# PRE_amp_16_5.net
KiCad netlist of a schematic drawn in EAGLE
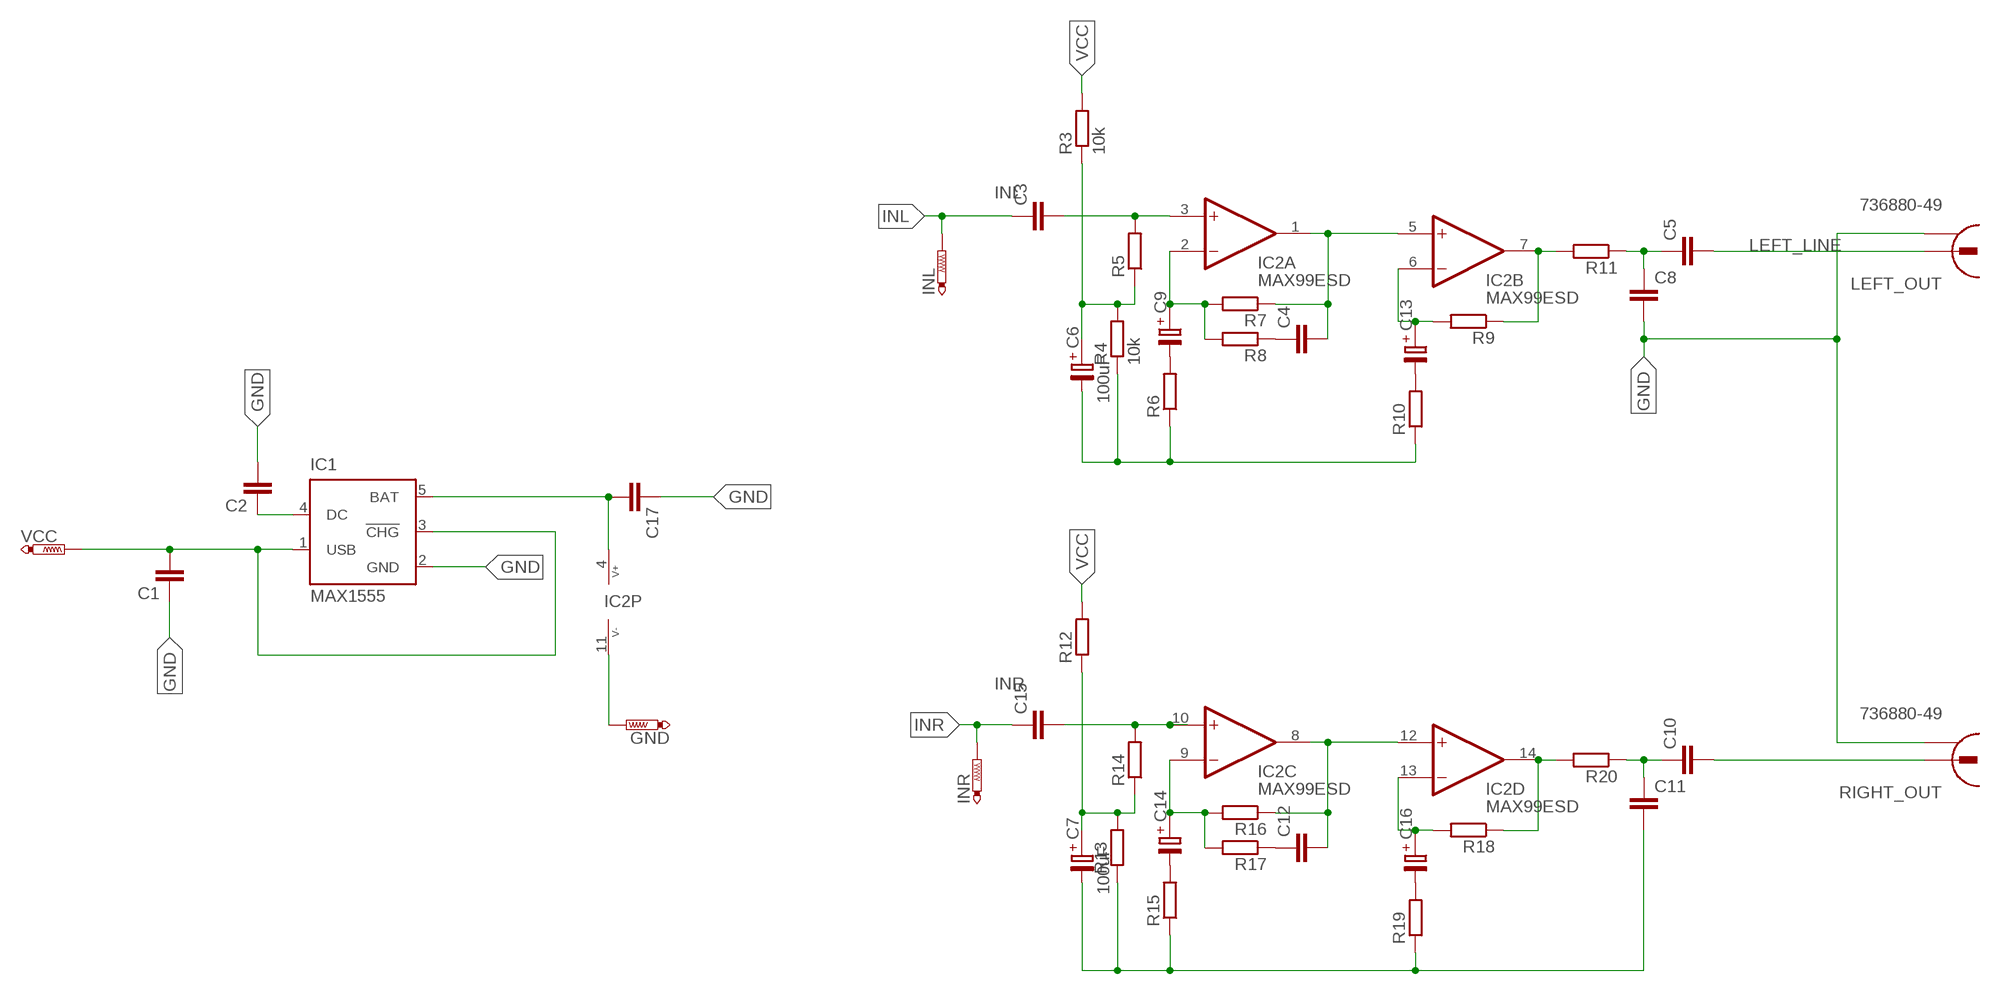
[diagram p0: schematic, sheet 1]

(export (version "E")
  (design (tool "Eeschema 10.0.6"))
  (components
    (comp (ref "C1")
      (value "C-EUC0805")
      (footprint "eagle-import:C0805")
      (libsource (lib "eagle-import") (part "C-EUC0805"))
    )
    (comp (ref "C2")
      (value "C-EUC0805")
      (footprint "eagle-import:C0805")
      (libsource (lib "eagle-import") (part "C-EUC0805"))
    )
    (comp (ref "C3")
      (value "C-EUC0805")
      (footprint "eagle-import:C0805")
      (libsource (lib "eagle-import") (part "C-EUC0805"))
    )
    (comp (ref "C4")
      (value "C-EUC0805")
      (footprint "eagle-import:C0805")
      (libsource (lib "eagle-import") (part "C-EUC0805"))
    )
    (comp (ref "C5")
      (value "C-EUC0805")
      (footprint "eagle-import:C0805")
      (libsource (lib "eagle-import") (part "C-EUC0805"))
    )
    (comp (ref "C6")
      (value "100uF")
      (footprint "eagle-import:SV-D")
      (libsource (lib "eagle-import") (part "C-PR-SMD-SV-D"))
    )
    (comp (ref "C7")
      (value "100uF")
      (footprint "eagle-import:SV-D")
      (libsource (lib "eagle-import") (part "C-PR-SMD-SV-D"))
    )
    (comp (ref "C8")
      (value "C-EUC0805")
      (footprint "eagle-import:C0805")
      (libsource (lib "eagle-import") (part "C-EUC0805"))
    )
    (comp (ref "C9")
      (value "C-PR-SMD-SV-B")
      (footprint "eagle-import:SV-B")
      (libsource (lib "eagle-import") (part "C-PR-SMD-SV-B"))
    )
    (comp (ref "C10")
      (value "C-EUC0805")
      (footprint "eagle-import:C0805")
      (libsource (lib "eagle-import") (part "C-EUC0805"))
    )
    (comp (ref "C11")
      (value "C-EUC0805")
      (footprint "eagle-import:C0805")
      (libsource (lib "eagle-import") (part "C-EUC0805"))
    )
    (comp (ref "C12")
      (value "C-EUC0805")
      (footprint "eagle-import:C0805")
      (libsource (lib "eagle-import") (part "C-EUC0805"))
    )
    (comp (ref "C13")
      (value "C-PR-SMD-SV-B")
      (footprint "eagle-import:SV-B")
      (libsource (lib "eagle-import") (part "C-PR-SMD-SV-B"))
    )
    (comp (ref "C14")
      (value "C-PR-SMD-SV-B")
      (footprint "eagle-import:SV-B")
      (libsource (lib "eagle-import") (part "C-PR-SMD-SV-B"))
    )
    (comp (ref "C15")
      (value "C-EUC0805")
      (footprint "eagle-import:C0805")
      (libsource (lib "eagle-import") (part "C-EUC0805"))
    )
    (comp (ref "C16")
      (value "C-PR-SMD-SV-B")
      (footprint "eagle-import:SV-B")
      (libsource (lib "eagle-import") (part "C-PR-SMD-SV-B"))
    )
    (comp (ref "C17")
      (value "C-EUC0805")
      (footprint "eagle-import:C0805")
      (libsource (lib "eagle-import") (part "C-EUC0805"))
    )
    (comp (ref "GND")
      (value "PTR1PAD1-13Y")
      (footprint "eagle-import:P1-13Y")
      (libsource (lib "eagle-import") (part "PTR1PAD1-13Y"))
    )
    (comp (ref "IC1")
      (value "MAX1555")
      (footprint "eagle-import:SOT23-5L")
      (libsource (lib "eagle-import") (part "MAX1555"))
    )
    (comp (ref "IC2")
      (value "MAX99ESD")
      (footprint "eagle-import:SO14")
      (libsource (lib "eagle-import") (part "MAX99ESD"))
    )
    (comp (ref "INL")
      (value "PTR1PAD1-13Y")
      (footprint "eagle-import:P1-13Y")
      (libsource (lib "eagle-import") (part "PTR1PAD1-13Y"))
    )
    (comp (ref "INR")
      (value "PTR1PAD1-13Y")
      (footprint "eagle-import:P1-13Y")
      (libsource (lib "eagle-import") (part "PTR1PAD1-13Y"))
    )
    (comp (ref "LEFT_OUT")
      (value "736880-49")
      (footprint "eagle-import:736880-49")
      (libsource (lib "eagle-import") (part "736880-49"))
    )
    (comp (ref "R3")
      (value "10k")
      (footprint "eagle-import:R1206")
      (libsource (lib "eagle-import") (part "R-EU_R1206"))
    )
    (comp (ref "R4")
      (value "10k")
      (footprint "eagle-import:R1206")
      (libsource (lib "eagle-import") (part "R-EU_R1206"))
    )
    (comp (ref "R5")
      (value "R-EU_R1206")
      (footprint "eagle-import:R1206")
      (libsource (lib "eagle-import") (part "R-EU_R1206"))
    )
    (comp (ref "R6")
      (value "R-EU_R1206")
      (footprint "eagle-import:R1206")
      (libsource (lib "eagle-import") (part "R-EU_R1206"))
    )
    (comp (ref "R7")
      (value "R-EU_R1206")
      (footprint "eagle-import:R1206")
      (libsource (lib "eagle-import") (part "R-EU_R1206"))
    )
    (comp (ref "R8")
      (value "R-EU_R1206")
      (footprint "eagle-import:R1206")
      (libsource (lib "eagle-import") (part "R-EU_R1206"))
    )
    (comp (ref "R9")
      (value "R-EU_R1206")
      (footprint "eagle-import:R1206")
      (libsource (lib "eagle-import") (part "R-EU_R1206"))
    )
    (comp (ref "R10")
      (value "R-EU_R1206")
      (footprint "eagle-import:R1206")
      (libsource (lib "eagle-import") (part "R-EU_R1206"))
    )
    (comp (ref "R11")
      (value "R-EU_R1206")
      (footprint "eagle-import:R1206")
      (libsource (lib "eagle-import") (part "R-EU_R1206"))
    )
    (comp (ref "R12")
      (value "R-EU_R1206")
      (footprint "eagle-import:R1206")
      (libsource (lib "eagle-import") (part "R-EU_R1206"))
    )
    (comp (ref "R13")
      (value "R-EU_R1206")
      (footprint "eagle-import:R1206")
      (libsource (lib "eagle-import") (part "R-EU_R1206"))
    )
    (comp (ref "R14")
      (value "R-EU_R1206")
      (footprint "eagle-import:R1206")
      (libsource (lib "eagle-import") (part "R-EU_R1206"))
    )
    (comp (ref "R15")
      (value "R-EU_R1206")
      (footprint "eagle-import:R1206")
      (libsource (lib "eagle-import") (part "R-EU_R1206"))
    )
    (comp (ref "R16")
      (value "R-EU_R1206")
      (footprint "eagle-import:R1206")
      (libsource (lib "eagle-import") (part "R-EU_R1206"))
    )
    (comp (ref "R17")
      (value "R-EU_R1206")
      (footprint "eagle-import:R1206")
      (libsource (lib "eagle-import") (part "R-EU_R1206"))
    )
    (comp (ref "R18")
      (value "R-EU_R1206")
      (footprint "eagle-import:R1206")
      (libsource (lib "eagle-import") (part "R-EU_R1206"))
    )
    (comp (ref "R19")
      (value "R-EU_R1206")
      (footprint "eagle-import:R1206")
      (libsource (lib "eagle-import") (part "R-EU_R1206"))
    )
    (comp (ref "R20")
      (value "R-EU_R1206")
      (footprint "eagle-import:R1206")
      (libsource (lib "eagle-import") (part "R-EU_R1206"))
    )
    (comp (ref "RIGHT_OUT")
      (value "736880-49")
      (footprint "eagle-import:736880-49")
      (libsource (lib "eagle-import") (part "736880-49"))
    )
    (comp (ref "VCC")
      (value "PTR1PAD1-13Y")
      (footprint "eagle-import:P1-13Y")
      (libsource (lib "eagle-import") (part "PTR1PAD1-13Y"))
    )
  )
  (nets
    (net (code "1") (name "/LEFT_LINE") (class "Default")
      (node (ref "C5") (pin "2") (pinfunction "2_2") (pintype "passive"))
      (node (ref "LEFT_OUT") (pin "1") (pinfunction "1_1") (pintype "passive"))
    )
    (net (code "2") (name "GND") (class "Default")
      (node (ref "C1") (pin "1") (pinfunction "1_1") (pintype "passive"))
      (node (ref "C11") (pin "2") (pinfunction "2_2") (pintype "passive"))
      (node (ref "C17") (pin "1") (pinfunction "1_1") (pintype "passive"))
      (node (ref "C2") (pin "2") (pinfunction "2_2") (pintype "passive"))
      (node (ref "C6") (pin "-") (pinfunction "-_-") (pintype "passive"))
      (node (ref "C7") (pin "-") (pinfunction "-_-") (pintype "passive"))
      (node (ref "C8") (pin "2") (pinfunction "2_2") (pintype "passive"))
      (node (ref "GND") (pin "1") (pinfunction "TP_1") (pintype "input"))
      (node (ref "IC1") (pin "2") (pinfunction "GND_2") (pintype "power_in"))
      (node (ref "IC2") (pin "11") (pinfunction "V-_11") (pintype "power_in"))
      (node (ref "LEFT_OUT") (pin "2") (pinfunction "2_2") (pintype "passive"))
      (node (ref "R10") (pin "1") (pinfunction "1_1") (pintype "passive"))
      (node (ref "R13") (pin "1") (pinfunction "1_1") (pintype "passive"))
      (node (ref "R15") (pin "1") (pinfunction "1_1") (pintype "passive"))
      (node (ref "R19") (pin "1") (pinfunction "1_1") (pintype "passive"))
      (node (ref "R4") (pin "1") (pinfunction "1_1") (pintype "passive"))
      (node (ref "R6") (pin "1") (pinfunction "1_1") (pintype "passive"))
      (node (ref "RIGHT_OUT") (pin "2") (pinfunction "2_2") (pintype "passive"))
    )
    (net (code "3") (name "INL") (class "Default")
      (node (ref "C3") (pin "1") (pinfunction "1_1") (pintype "passive"))
      (node (ref "INL") (pin "1") (pinfunction "TP_1") (pintype "input"))
    )
    (net (code "4") (name "INR") (class "Default")
      (node (ref "C15") (pin "1") (pinfunction "1_1") (pintype "passive"))
      (node (ref "INR") (pin "1") (pinfunction "TP_1") (pintype "input"))
    )
    (net (code "5") (name "Net-(C4-Pad1)") (class "Default")
      (node (ref "C4") (pin "1") (pinfunction "1_1") (pintype "passive"))
      (node (ref "R8") (pin "1") (pinfunction "1_1") (pintype "passive"))
    )
    (net (code "6") (name "Net-(C5-Pad1)") (class "Default")
      (node (ref "C5") (pin "1") (pinfunction "1_1") (pintype "passive"))
      (node (ref "C8") (pin "1") (pinfunction "1_1") (pintype "passive"))
      (node (ref "R11") (pin "1") (pinfunction "1_1") (pintype "passive"))
    )
    (net (code "7") (name "Net-(C6-Pad+)") (class "Default")
      (node (ref "C6") (pin "+") (pinfunction "+_+") (pintype "passive"))
      (node (ref "R3") (pin "1") (pinfunction "1_1") (pintype "passive"))
      (node (ref "R4") (pin "2") (pinfunction "2_2") (pintype "passive"))
      (node (ref "R5") (pin "1") (pinfunction "1_1") (pintype "passive"))
    )
    (net (code "8") (name "Net-(C7-Pad+)") (class "Default")
      (node (ref "C7") (pin "+") (pinfunction "+_+") (pintype "passive"))
      (node (ref "R12") (pin "1") (pinfunction "1_1") (pintype "passive"))
      (node (ref "R13") (pin "2") (pinfunction "2_2") (pintype "passive"))
      (node (ref "R14") (pin "1") (pinfunction "1_1") (pintype "passive"))
    )
    (net (code "9") (name "Net-(C9-Pad-)") (class "Default")
      (node (ref "C9") (pin "-") (pinfunction "-_-") (pintype "passive"))
      (node (ref "R6") (pin "2") (pinfunction "2_2") (pintype "passive"))
    )
    (net (code "10") (name "Net-(C10-Pad1)") (class "Default")
      (node (ref "C10") (pin "1") (pinfunction "1_1") (pintype "passive"))
      (node (ref "C11") (pin "1") (pinfunction "1_1") (pintype "passive"))
      (node (ref "R20") (pin "1") (pinfunction "1_1") (pintype "passive"))
    )
    (net (code "11") (name "Net-(C10-Pad2)") (class "Default")
      (node (ref "C10") (pin "2") (pinfunction "2_2") (pintype "passive"))
      (node (ref "RIGHT_OUT") (pin "1") (pinfunction "1_1") (pintype "passive"))
    )
    (net (code "12") (name "Net-(C12-Pad1)") (class "Default")
      (node (ref "C12") (pin "1") (pinfunction "1_1") (pintype "passive"))
      (node (ref "R17") (pin "1") (pinfunction "1_1") (pintype "passive"))
    )
    (net (code "13") (name "Net-(C13-Pad-)") (class "Default")
      (node (ref "C13") (pin "-") (pinfunction "-_-") (pintype "passive"))
      (node (ref "R10") (pin "2") (pinfunction "2_2") (pintype "passive"))
    )
    (net (code "14") (name "Net-(C14-Pad-)") (class "Default")
      (node (ref "C14") (pin "-") (pinfunction "-_-") (pintype "passive"))
      (node (ref "R15") (pin "2") (pinfunction "2_2") (pintype "passive"))
    )
    (net (code "15") (name "Net-(C16-Pad-)") (class "Default")
      (node (ref "C16") (pin "-") (pinfunction "-_-") (pintype "passive"))
      (node (ref "R19") (pin "2") (pinfunction "2_2") (pintype "passive"))
    )
    (net (code "16") (name "Net-(IC1-BAT)") (class "Default")
      (node (ref "C17") (pin "2") (pinfunction "2_2") (pintype "passive"))
      (node (ref "IC1") (pin "5") (pinfunction "BAT_5") (pintype "passive"))
      (node (ref "IC2") (pin "4") (pinfunction "V+_4") (pintype "power_in"))
    )
    (net (code "17") (name "Net-(IC1-DC)") (class "Default")
      (node (ref "C2") (pin "1") (pinfunction "1_1") (pintype "passive"))
      (node (ref "IC1") (pin "4") (pinfunction "DC_4") (pintype "input"))
    )
    (net (code "18") (name "Net-(IC1-USB)") (class "Default")
      (node (ref "C1") (pin "2") (pinfunction "2_2") (pintype "passive"))
      (node (ref "IC1") (pin "1") (pinfunction "USB_1") (pintype "input"))
      (node (ref "IC1") (pin "3") (pinfunction "~{CHG}_3") (pintype "output"))
      (node (ref "VCC") (pin "1") (pinfunction "TP_1") (pintype "input"))
    )
    (net (code "19") (name "Net-(IC2A-+IN)") (class "Default")
      (node (ref "C3") (pin "2") (pinfunction "2_2") (pintype "passive"))
      (node (ref "IC2") (pin "3") (pinfunction "+IN_3") (pintype "input"))
      (node (ref "R5") (pin "2") (pinfunction "2_2") (pintype "passive"))
    )
    (net (code "20") (name "Net-(IC2A--IN)") (class "Default")
      (node (ref "C9") (pin "+") (pinfunction "+_+") (pintype "passive"))
      (node (ref "IC2") (pin "2") (pinfunction "-IN_2") (pintype "input"))
      (node (ref "R7") (pin "2") (pinfunction "2_2") (pintype "passive"))
      (node (ref "R8") (pin "2") (pinfunction "2_2") (pintype "passive"))
    )
    (net (code "21") (name "Net-(IC2A-OUT)") (class "Default")
      (node (ref "C4") (pin "2") (pinfunction "2_2") (pintype "passive"))
      (node (ref "IC2") (pin "1") (pinfunction "OUT_1") (pintype "output"))
      (node (ref "IC2") (pin "5") (pinfunction "+IN_5") (pintype "input"))
      (node (ref "R7") (pin "1") (pinfunction "1_1") (pintype "passive"))
    )
    (net (code "22") (name "Net-(IC2B--IN)") (class "Default")
      (node (ref "C13") (pin "+") (pinfunction "+_+") (pintype "passive"))
      (node (ref "IC2") (pin "6") (pinfunction "-IN_6") (pintype "input"))
      (node (ref "R9") (pin "2") (pinfunction "2_2") (pintype "passive"))
    )
    (net (code "23") (name "Net-(IC2B-OUT)") (class "Default")
      (node (ref "IC2") (pin "7") (pinfunction "OUT_7") (pintype "output"))
      (node (ref "R11") (pin "2") (pinfunction "2_2") (pintype "passive"))
      (node (ref "R9") (pin "1") (pinfunction "1_1") (pintype "passive"))
    )
    (net (code "24") (name "Net-(IC2C-+IN)") (class "Default")
      (node (ref "C15") (pin "2") (pinfunction "2_2") (pintype "passive"))
      (node (ref "IC2") (pin "10") (pinfunction "+IN_10") (pintype "input"))
      (node (ref "R14") (pin "2") (pinfunction "2_2") (pintype "passive"))
    )
    (net (code "25") (name "Net-(IC2C--IN)") (class "Default")
      (node (ref "C14") (pin "+") (pinfunction "+_+") (pintype "passive"))
      (node (ref "IC2") (pin "9") (pinfunction "-IN_9") (pintype "input"))
      (node (ref "R16") (pin "2") (pinfunction "2_2") (pintype "passive"))
      (node (ref "R17") (pin "2") (pinfunction "2_2") (pintype "passive"))
    )
    (net (code "26") (name "Net-(IC2C-OUT)") (class "Default")
      (node (ref "C12") (pin "2") (pinfunction "2_2") (pintype "passive"))
      (node (ref "IC2") (pin "12") (pinfunction "+IN_12") (pintype "input"))
      (node (ref "IC2") (pin "8") (pinfunction "OUT_8") (pintype "output"))
      (node (ref "R16") (pin "1") (pinfunction "1_1") (pintype "passive"))
    )
    (net (code "27") (name "Net-(IC2D--IN)") (class "Default")
      (node (ref "C16") (pin "+") (pinfunction "+_+") (pintype "passive"))
      (node (ref "IC2") (pin "13") (pinfunction "-IN_13") (pintype "input"))
      (node (ref "R18") (pin "2") (pinfunction "2_2") (pintype "passive"))
    )
    (net (code "28") (name "Net-(IC2D-OUT)") (class "Default")
      (node (ref "IC2") (pin "14") (pinfunction "OUT_14") (pintype "output"))
      (node (ref "R18") (pin "1") (pinfunction "1_1") (pintype "passive"))
      (node (ref "R20") (pin "2") (pinfunction "2_2") (pintype "passive"))
    )
    (net (code "29") (name "VCC") (class "Default")
      (node (ref "R12") (pin "2") (pinfunction "2_2") (pintype "passive"))
      (node (ref "R3") (pin "2") (pinfunction "2_2") (pintype "passive"))
    )
    (net (code "30") (name "unconnected-(LEFT_OUT-2-Pad2@2)") (class "Default")
      (node (ref "LEFT_OUT") (pin "2@2") (pinfunction "2_2@2") (pintype "passive"))
    )
    (net (code "31") (name "unconnected-(RIGHT_OUT-2-Pad2@2)") (class "Default")
      (node (ref "RIGHT_OUT") (pin "2@2") (pinfunction "2_2@2") (pintype "passive"))
    )
  )
)
